# Tinyusbboard_rev3_THT.net
KiCad netlist of a schematic drawn in EAGLE
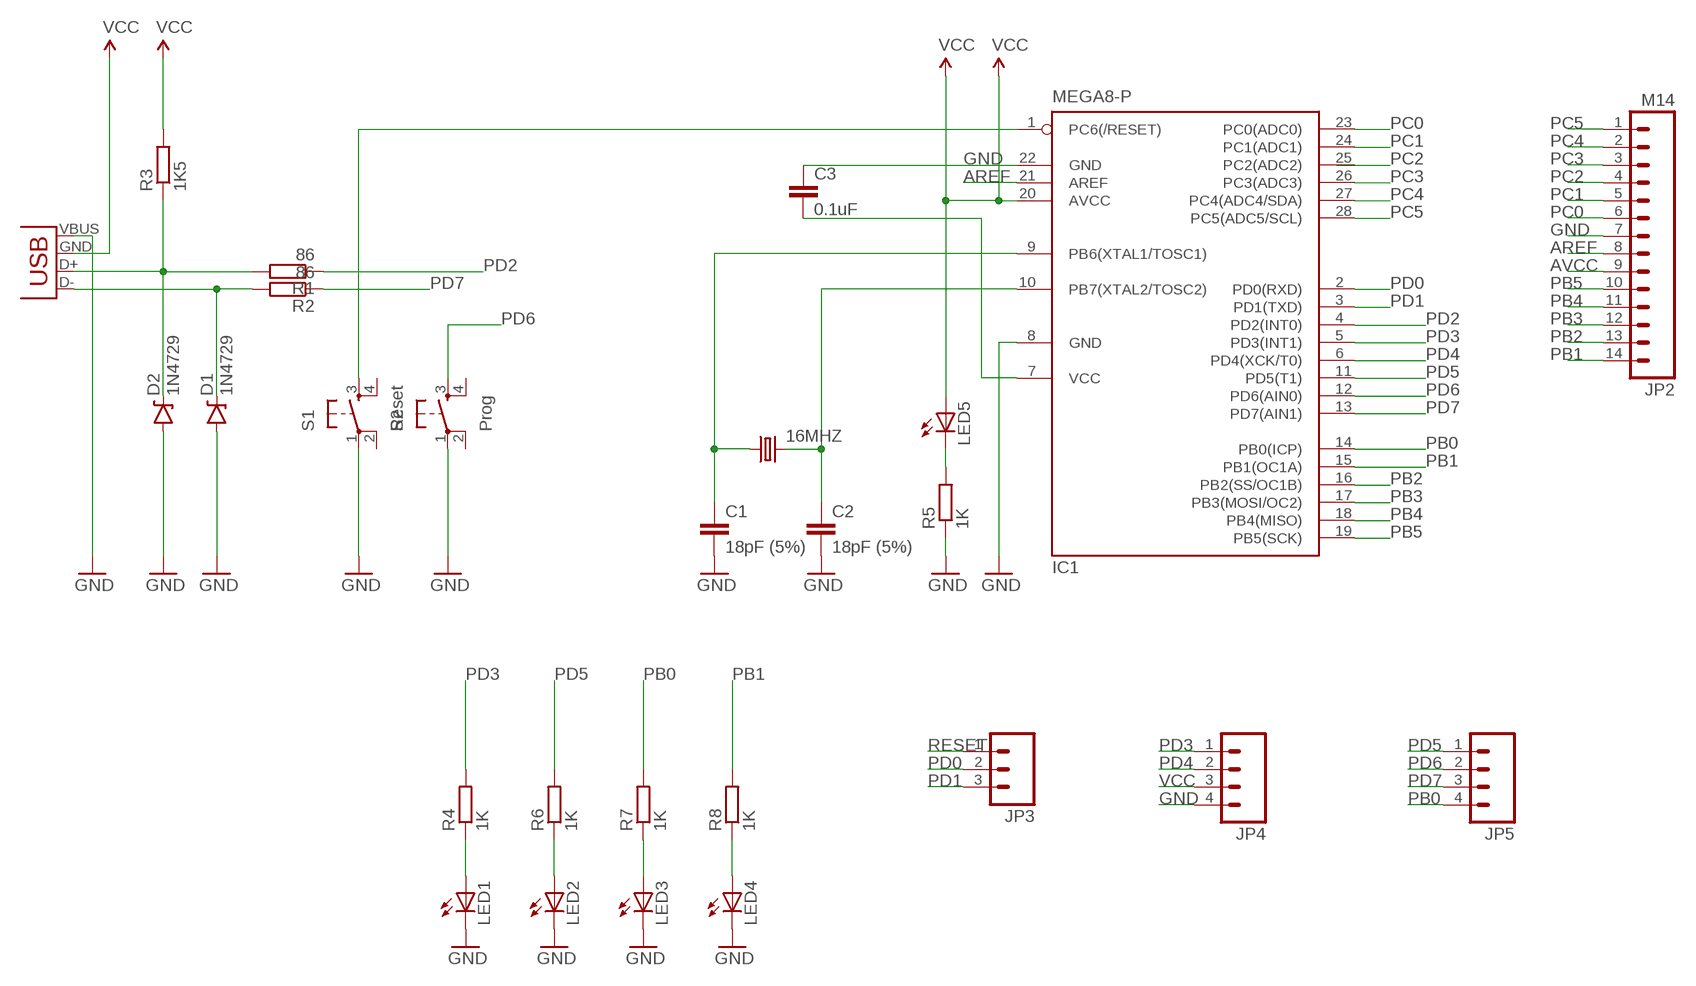
[diagram p0: schematic, sheet 1]

(export (version "E")
  (design (tool "Eeschema 10.0.6"))
  (components
    (comp (ref "16MHZ")
      (value "CRYSTALTC26V")
      (footprint "eagle-import:TC26V")
      (libsource (lib "eagle-import") (part "CRYSTALTC26V"))
    )
    (comp (ref "C1")
      (value "18pF (5%)")
      (footprint "eagle-import:C025-024X044")
      (libsource (lib "eagle-import") (part "C-EU025-024X044"))
    )
    (comp (ref "C2")
      (value "18pF (5%)")
      (footprint "eagle-import:C025-024X044")
      (libsource (lib "eagle-import") (part "C-EU025-024X044"))
    )
    (comp (ref "C3")
      (value "0.1uF")
      (footprint "eagle-import:C025-024X044")
      (libsource (lib "eagle-import") (part "C-EU025-024X044"))
    )
    (comp (ref "D1")
      (value "1N4729")
      (footprint "eagle-import:DIODE-ZENER")
      (libsource (lib "eagle-import") (part "DIODE-ZENERPTH"))
    )
    (comp (ref "D2")
      (value "1N4729")
      (footprint "eagle-import:DIODE-ZENER")
      (libsource (lib "eagle-import") (part "DIODE-ZENERPTH"))
    )
    (comp (ref "IC1")
      (value "MEGA8-P")
      (footprint "eagle-import:DIL28-3")
      (libsource (lib "eagle-import") (part "MEGA8-P"))
    )
    (comp (ref "JP1")
      (value "USB-A-H")
      (footprint "eagle-import:USB-A-H")
      (libsource (lib "eagle-import") (part "USB-A-H"))
    )
    (comp (ref "JP2")
      (value "M14")
      (footprint "eagle-import:1X14")
      (libsource (lib "eagle-import") (part "M14"))
    )
    (comp (ref "JP3")
      (value "M03PTH")
      (footprint "eagle-import:1X03")
      (libsource (lib "eagle-import") (part "M03PTH"))
    )
    (comp (ref "JP4")
      (value "M04PTH")
      (footprint "eagle-import:1X04")
      (libsource (lib "eagle-import") (part "M04PTH"))
    )
    (comp (ref "JP5")
      (value "M04PTH")
      (footprint "eagle-import:1X04")
      (libsource (lib "eagle-import") (part "M04PTH"))
    )
    (comp (ref "LED1")
      (value "LED3MM")
      (footprint "eagle-import:LED3MM")
      (libsource (lib "eagle-import") (part "LED3MM"))
    )
    (comp (ref "LED2")
      (value "LED3MM")
      (footprint "eagle-import:LED3MM")
      (libsource (lib "eagle-import") (part "LED3MM"))
    )
    (comp (ref "LED3")
      (value "LED3MM")
      (footprint "eagle-import:LED3MM")
      (libsource (lib "eagle-import") (part "LED3MM"))
    )
    (comp (ref "LED4")
      (value "LED3MM")
      (footprint "eagle-import:LED3MM")
      (libsource (lib "eagle-import") (part "LED3MM"))
    )
    (comp (ref "LED5")
      (value "LED3MM")
      (footprint "eagle-import:LED3MM")
      (libsource (lib "eagle-import") (part "LED3MM"))
    )
    (comp (ref "R1")
      (value "86")
      (footprint "eagle-import:0204_7")
      (libsource (lib "eagle-import") (part "R-EU_0204/7"))
    )
    (comp (ref "R2")
      (value "86")
      (footprint "eagle-import:0204_7")
      (libsource (lib "eagle-import") (part "R-EU_0204/7"))
    )
    (comp (ref "R3")
      (value "1K5")
      (footprint "eagle-import:0204_7")
      (libsource (lib "eagle-import") (part "R-EU_0204/7"))
    )
    (comp (ref "R4")
      (value "1K")
      (footprint "eagle-import:0204_7")
      (libsource (lib "eagle-import") (part "R-EU_0204/7"))
    )
    (comp (ref "R5")
      (value "1K")
      (footprint "eagle-import:0204_7")
      (libsource (lib "eagle-import") (part "R-EU_0204/7"))
    )
    (comp (ref "R6")
      (value "1K")
      (footprint "eagle-import:0204V")
      (libsource (lib "eagle-import") (part "R-EU_0204/2V"))
    )
    (comp (ref "R7")
      (value "1K")
      (footprint "eagle-import:0204V")
      (libsource (lib "eagle-import") (part "R-EU_0204/2V"))
    )
    (comp (ref "R8")
      (value "1K")
      (footprint "eagle-import:0204_7")
      (libsource (lib "eagle-import") (part "R-EU_0204/7"))
    )
    (comp (ref "S1")
      (value "Reset")
      (footprint "eagle-import:TACTILE-PTH")
      (libsource (lib "eagle-import") (part "TAC_SWITCHPTH"))
    )
    (comp (ref "S2")
      (value "Prog")
      (footprint "eagle-import:TACTILE-PTH")
      (libsource (lib "eagle-import") (part "TAC_SWITCHPTH"))
    )
  )
  (nets
    (net (code "1") (name "/AREF") (class "Default")
      (node (ref "IC1") (pin "21") (pinfunction "AREF_21") (pintype "passive"))
      (node (ref "JP2") (pin "8") (pinfunction "8_8") (pintype "passive"))
    )
    (net (code "2") (name "/AVCC") (class "Default")
      (node (ref "JP2") (pin "9") (pinfunction "9_9") (pintype "passive"))
    )
    (net (code "3") (name "/PB0") (class "Default")
      (node (ref "IC1") (pin "14") (pinfunction "PB0(ICP)_14") (pintype "bidirectional"))
      (node (ref "JP5") (pin "4") (pinfunction "4_4") (pintype "passive"))
      (node (ref "R7") (pin "2") (pinfunction "2_2") (pintype "passive"))
    )
    (net (code "4") (name "/PB1") (class "Default")
      (node (ref "IC1") (pin "15") (pinfunction "PB1(OC1A)_15") (pintype "bidirectional"))
      (node (ref "JP2") (pin "14") (pinfunction "14_14") (pintype "passive"))
      (node (ref "R8") (pin "2") (pinfunction "2_2") (pintype "passive"))
    )
    (net (code "5") (name "/PB2") (class "Default")
      (node (ref "IC1") (pin "16") (pinfunction "PB2(SS/OC1B)_16") (pintype "bidirectional"))
      (node (ref "JP2") (pin "13") (pinfunction "13_13") (pintype "passive"))
    )
    (net (code "6") (name "/PB3") (class "Default")
      (node (ref "IC1") (pin "17") (pinfunction "PB3(MOSI/OC2)_17") (pintype "bidirectional"))
      (node (ref "JP2") (pin "12") (pinfunction "12_12") (pintype "passive"))
    )
    (net (code "7") (name "/PB4") (class "Default")
      (node (ref "IC1") (pin "18") (pinfunction "PB4(MISO)_18") (pintype "bidirectional"))
      (node (ref "JP2") (pin "11") (pinfunction "11_11") (pintype "passive"))
    )
    (net (code "8") (name "/PB5") (class "Default")
      (node (ref "IC1") (pin "19") (pinfunction "PB5(SCK)_19") (pintype "bidirectional"))
      (node (ref "JP2") (pin "10") (pinfunction "10_10") (pintype "passive"))
    )
    (net (code "9") (name "/PC0") (class "Default")
      (node (ref "IC1") (pin "23") (pinfunction "PC0(ADC0)_23") (pintype "bidirectional"))
      (node (ref "JP2") (pin "6") (pinfunction "6_6") (pintype "passive"))
    )
    (net (code "10") (name "/PC1") (class "Default")
      (node (ref "IC1") (pin "24") (pinfunction "PC1(ADC1)_24") (pintype "bidirectional"))
      (node (ref "JP2") (pin "5") (pinfunction "5_5") (pintype "passive"))
    )
    (net (code "11") (name "/PC2") (class "Default")
      (node (ref "IC1") (pin "25") (pinfunction "PC2(ADC2)_25") (pintype "bidirectional"))
      (node (ref "JP2") (pin "4") (pinfunction "4_4") (pintype "passive"))
    )
    (net (code "12") (name "/PC3") (class "Default")
      (node (ref "IC1") (pin "26") (pinfunction "PC3(ADC3)_26") (pintype "bidirectional"))
      (node (ref "JP2") (pin "3") (pinfunction "3_3") (pintype "passive"))
    )
    (net (code "13") (name "/PC4") (class "Default")
      (node (ref "IC1") (pin "27") (pinfunction "PC4(ADC4/SDA)_27") (pintype "bidirectional"))
      (node (ref "JP2") (pin "2") (pinfunction "2_2") (pintype "passive"))
    )
    (net (code "14") (name "/PC5") (class "Default")
      (node (ref "IC1") (pin "28") (pinfunction "PC5(ADC5/SCL)_28") (pintype "bidirectional"))
      (node (ref "JP2") (pin "1") (pinfunction "1_1") (pintype "passive"))
    )
    (net (code "15") (name "/PD0") (class "Default")
      (node (ref "IC1") (pin "2") (pinfunction "PD0(RXD)_2") (pintype "bidirectional"))
      (node (ref "JP3") (pin "2") (pinfunction "2_2") (pintype "passive"))
    )
    (net (code "16") (name "/PD1") (class "Default")
      (node (ref "IC1") (pin "3") (pinfunction "PD1(TXD)_3") (pintype "bidirectional"))
      (node (ref "JP3") (pin "3") (pinfunction "3_3") (pintype "passive"))
    )
    (net (code "17") (name "/PD2") (class "Default")
      (node (ref "IC1") (pin "4") (pinfunction "PD2(INT0)_4") (pintype "bidirectional"))
      (node (ref "R1") (pin "1") (pinfunction "1_1") (pintype "passive"))
    )
    (net (code "18") (name "/PD3") (class "Default")
      (node (ref "IC1") (pin "5") (pinfunction "PD3(INT1)_5") (pintype "bidirectional"))
      (node (ref "JP4") (pin "1") (pinfunction "1_1") (pintype "passive"))
      (node (ref "R4") (pin "2") (pinfunction "2_2") (pintype "passive"))
    )
    (net (code "19") (name "/PD4") (class "Default")
      (node (ref "IC1") (pin "6") (pinfunction "PD4(XCK/T0)_6") (pintype "bidirectional"))
      (node (ref "JP4") (pin "2") (pinfunction "2_2") (pintype "passive"))
    )
    (net (code "20") (name "/PD5") (class "Default")
      (node (ref "IC1") (pin "11") (pinfunction "PD5(T1)_11") (pintype "bidirectional"))
      (node (ref "JP5") (pin "1") (pinfunction "1_1") (pintype "passive"))
      (node (ref "R6") (pin "2") (pinfunction "2_2") (pintype "passive"))
    )
    (net (code "21") (name "/PD6") (class "Default")
      (node (ref "IC1") (pin "12") (pinfunction "PD6(AIN0)_12") (pintype "bidirectional"))
      (node (ref "JP5") (pin "2") (pinfunction "2_2") (pintype "passive"))
      (node (ref "S2") (pin "3") (pinfunction "3_3") (pintype "passive"))
    )
    (net (code "22") (name "/PD7") (class "Default")
      (node (ref "IC1") (pin "13") (pinfunction "PD7(AIN1)_13") (pintype "bidirectional"))
      (node (ref "JP5") (pin "3") (pinfunction "3_3") (pintype "passive"))
      (node (ref "R2") (pin "1") (pinfunction "1_1") (pintype "passive"))
    )
    (net (code "23") (name "/RESET") (class "Default")
      (node (ref "IC1") (pin "1") (pinfunction "PC6(/RESET)_1") (pintype "bidirectional"))
      (node (ref "JP3") (pin "1") (pinfunction "1_1") (pintype "passive"))
      (node (ref "S1") (pin "3") (pinfunction "3_3") (pintype "passive"))
    )
    (net (code "24") (name "GND") (class "Default")
      (node (ref "C1") (pin "2") (pinfunction "2_2") (pintype "passive"))
      (node (ref "C2") (pin "2") (pinfunction "2_2") (pintype "passive"))
      (node (ref "C3") (pin "1") (pinfunction "1_1") (pintype "passive"))
      (node (ref "D1") (pin "P$2") (pinfunction "A_P$2") (pintype "passive"))
      (node (ref "D2") (pin "P$2") (pinfunction "A_P$2") (pintype "passive"))
      (node (ref "IC1") (pin "22") (pinfunction "GND_22") (pintype "power_in"))
      (node (ref "IC1") (pin "8") (pinfunction "GND_8") (pintype "power_in"))
      (node (ref "JP1") (pin "VBUS") (pinfunction "GND_VBUS") (pintype "bidirectional"))
      (node (ref "JP2") (pin "7") (pinfunction "7_7") (pintype "passive"))
      (node (ref "JP4") (pin "4") (pinfunction "4_4") (pintype "passive"))
      (node (ref "LED1") (pin "K") (pinfunction "C_K") (pintype "passive"))
      (node (ref "LED2") (pin "K") (pinfunction "C_K") (pintype "passive"))
      (node (ref "LED3") (pin "K") (pinfunction "C_K") (pintype "passive"))
      (node (ref "LED4") (pin "K") (pinfunction "C_K") (pintype "passive"))
      (node (ref "R5") (pin "1") (pinfunction "1_1") (pintype "passive"))
      (node (ref "S1") (pin "1") (pinfunction "1_1") (pintype "passive"))
      (node (ref "S2") (pin "1") (pinfunction "1_1") (pintype "passive"))
    )
    (net (code "25") (name "Net-(D1-C)") (class "Default")
      (node (ref "D1") (pin "P$1") (pinfunction "C_P$1") (pintype "passive"))
      (node (ref "JP1") (pin "D-") (pinfunction "D+_D-") (pintype "bidirectional"))
      (node (ref "R2") (pin "2") (pinfunction "2_2") (pintype "passive"))
    )
    (net (code "26") (name "Net-(D2-C)") (class "Default")
      (node (ref "D2") (pin "P$1") (pinfunction "C_P$1") (pintype "passive"))
      (node (ref "JP1") (pin "D+") (pinfunction "D-_D+") (pintype "bidirectional"))
      (node (ref "R1") (pin "2") (pinfunction "2_2") (pintype "passive"))
      (node (ref "R3") (pin "1") (pinfunction "1_1") (pintype "passive"))
    )
    (net (code "27") (name "Net-(IC1-PB6(XTAL1{slash}TOSC1))") (class "Default")
      (node (ref "16MHZ") (pin "1") (pinfunction "1_1") (pintype "passive"))
      (node (ref "C1") (pin "1") (pinfunction "1_1") (pintype "passive"))
      (node (ref "IC1") (pin "9") (pinfunction "PB6(XTAL1/TOSC1)_9") (pintype "bidirectional"))
    )
    (net (code "28") (name "Net-(IC1-PB7(XTAL2{slash}TOSC2))") (class "Default")
      (node (ref "16MHZ") (pin "2") (pinfunction "2_2") (pintype "passive"))
      (node (ref "C2") (pin "1") (pinfunction "1_1") (pintype "passive"))
      (node (ref "IC1") (pin "10") (pinfunction "PB7(XTAL2/TOSC2)_10") (pintype "bidirectional"))
    )
    (net (code "29") (name "Net-(IC1-VCC)") (class "Default")
      (node (ref "C3") (pin "2") (pinfunction "2_2") (pintype "passive"))
      (node (ref "IC1") (pin "7") (pinfunction "VCC_7") (pintype "power_in"))
    )
    (net (code "30") (name "Net-(LED1-PadA)") (class "Default")
      (node (ref "LED1") (pin "A") (pinfunction "A_A") (pintype "passive"))
      (node (ref "R4") (pin "1") (pinfunction "1_1") (pintype "passive"))
    )
    (net (code "31") (name "Net-(LED2-PadA)") (class "Default")
      (node (ref "LED2") (pin "A") (pinfunction "A_A") (pintype "passive"))
      (node (ref "R6") (pin "1") (pinfunction "1_1") (pintype "passive"))
    )
    (net (code "32") (name "Net-(LED3-PadA)") (class "Default")
      (node (ref "LED3") (pin "A") (pinfunction "A_A") (pintype "passive"))
      (node (ref "R7") (pin "1") (pinfunction "1_1") (pintype "passive"))
    )
    (net (code "33") (name "Net-(LED4-PadA)") (class "Default")
      (node (ref "LED4") (pin "A") (pinfunction "A_A") (pintype "passive"))
      (node (ref "R8") (pin "1") (pinfunction "1_1") (pintype "passive"))
    )
    (net (code "34") (name "Net-(LED5-C)") (class "Default")
      (node (ref "LED5") (pin "K") (pinfunction "C_K") (pintype "passive"))
      (node (ref "R5") (pin "2") (pinfunction "2_2") (pintype "passive"))
    )
    (net (code "35") (name "VCC") (class "Default")
      (node (ref "IC1") (pin "20") (pinfunction "AVCC_20") (pintype "power_in"))
      (node (ref "JP1") (pin "GND") (pinfunction "VBUS_GND") (pintype "bidirectional"))
      (node (ref "JP4") (pin "3") (pinfunction "3_3") (pintype "passive"))
      (node (ref "LED5") (pin "A") (pinfunction "A_A") (pintype "passive"))
      (node (ref "R3") (pin "2") (pinfunction "2_2") (pintype "passive"))
    )
    (net (code "36") (name "unconnected-(S1-Pad2)") (class "Default")
      (node (ref "S1") (pin "2") (pinfunction "2_2") (pintype "passive"))
    )
    (net (code "37") (name "unconnected-(S1-Pad4)") (class "Default")
      (node (ref "S1") (pin "4") (pinfunction "4_4") (pintype "passive"))
    )
    (net (code "38") (name "unconnected-(S2-Pad2)") (class "Default")
      (node (ref "S2") (pin "2") (pinfunction "2_2") (pintype "passive"))
    )
    (net (code "39") (name "unconnected-(S2-Pad4)") (class "Default")
      (node (ref "S2") (pin "4") (pinfunction "4_4") (pintype "passive"))
    )
  )
)
